# Sch_pwr_brd_pwr.net
KiCad netlist of a schematic drawn in Altium Designer
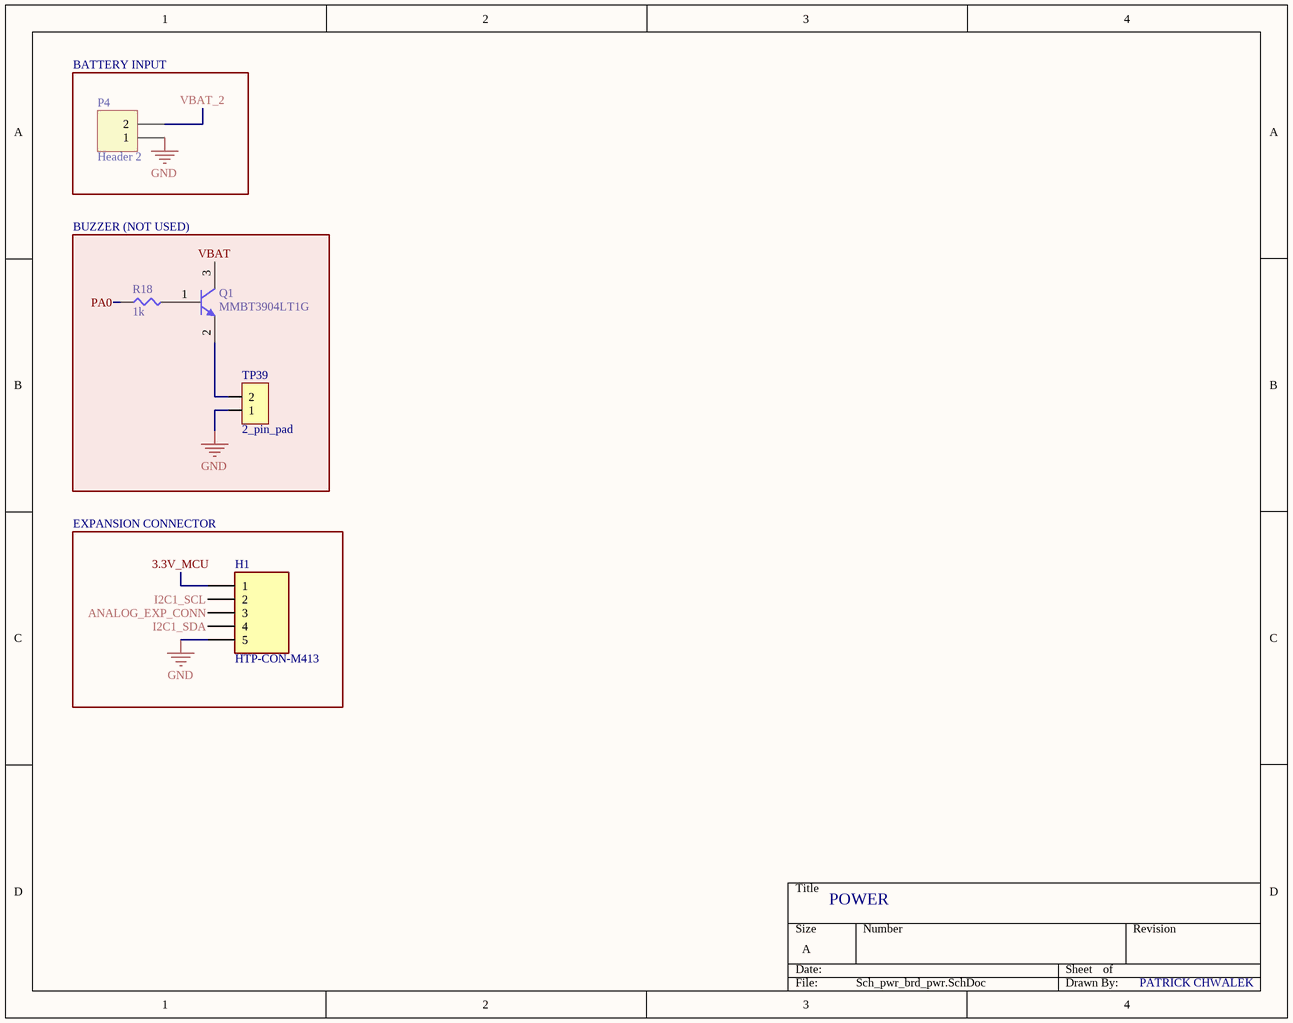
[diagram p0: Sch_pwr_brd_pwr.SchDoc]

(export (version "E")
  (design (tool "Eeschema 10.0.6"))
  (components
    (comp (ref "H1")
      (value "HTP-CON-M413")
      (footprint "SamacSys:HTP-CON-M413")
      (libsource (lib "SamacSys") (part "HTP-CON-M413"))
    )
    (comp (ref "P4")
      (value "Header 2")
      (footprint "HDR1X2")
      (description "Header, 2-Pin")
      (fields (field (name "PUBLISHER") "Altium Limited"))
      (libsource (lib "Miscellaneous Connectors") (part "Header 2"))
    )
    (comp (ref "Q1")
      (value "MMBT3904LT1G")
      (footprint "ONSC-SOT-23-3-318-08_V")
      (description "General Purpose Transistor, NPN Silicon, 3-Pin SOT-23, Pb-Free, Tape and Reel")
      (fields (field (name "MANUFACTURER") "On Semiconductor"))
      (libsource (lib "Altium Content Vault") (part "ONSC-NPN-B1E2C3-3"))
    )
    (comp (ref "R18")
      (value "1k")
      (footprint "SMD-0402-RES")
      (description "RES SMD 1K OHM 5% 1/10W 0402")
      (fields (field (name "PART NUMBER") "ERJ-2GEJ102X") (field (name "DIGI-KEY PART NUMBER") "P1.0KJCT-ND"))
      (libsource (lib "Panasonic_ERJ_0402") (part "ERJ-2GEJ102X"))
    )
    (comp (ref "TP39")
      (value "2_pin_pad")
      (footprint "Edge Connector (2-mini)")
      (libsource (lib "schematic_components") (part "2_pin_pad"))
    )
  )
  (nets
    (net (code "1") (name "/3.3V_MCU") (class "Default")
      (node (ref "H1") (pin "1") (pinfunction "1_1") (pintype "passive"))
    )
    (net (code "3") (name "/ANALOG_EXP_CONN") (class "Default")
      (node (ref "H1") (pin "3") (pinfunction "3_3") (pintype "passive"))
    )
    (net (code "4") (name "/I2C1_SCL") (class "Default")
      (node (ref "H1") (pin "2") (pinfunction "2_2") (pintype "passive"))
    )
    (net (code "5") (name "/I2C1_SDA") (class "Default")
      (node (ref "H1") (pin "4") (pinfunction "4_4") (pintype "passive"))
    )
    (net (code "6") (name "/PA0") (class "Default")
      (node (ref "R18") (pin "1") (pinfunction "1_1") (pintype "passive"))
    )
    (net (code "7") (name "/VBAT") (class "Default")
      (node (ref "Q1") (pin "3") (pinfunction "C_3") (pintype "passive"))
    )
    (net (code "8") (name "/VBAT_2") (class "Default")
      (node (ref "P4") (pin "2") (pinfunction "2_2") (pintype "passive"))
    )
    (net (code "9") (name "GND") (class "Default")
      (node (ref "H1") (pin "5") (pinfunction "5_5") (pintype "passive"))
      (node (ref "P4") (pin "1") (pinfunction "1_1") (pintype "passive"))
      (node (ref "TP39") (pin "1") (pinfunction "1_1") (pintype "passive"))
    )
    (net (code "10") (name "Net-(Q1-B)") (class "Default")
      (node (ref "Q1") (pin "1") (pinfunction "B_1") (pintype "passive"))
      (node (ref "R18") (pin "2") (pinfunction "2_2") (pintype "passive"))
    )
    (net (code "11") (name "Net-(Q1-E)") (class "Default")
      (node (ref "Q1") (pin "2") (pinfunction "E_2") (pintype "passive"))
      (node (ref "TP39") (pin "2") (pinfunction "2_2") (pintype "passive"))
    )
  )
)
